# Top.net
KiCad netlist of a schematic drawn in EasyEDA
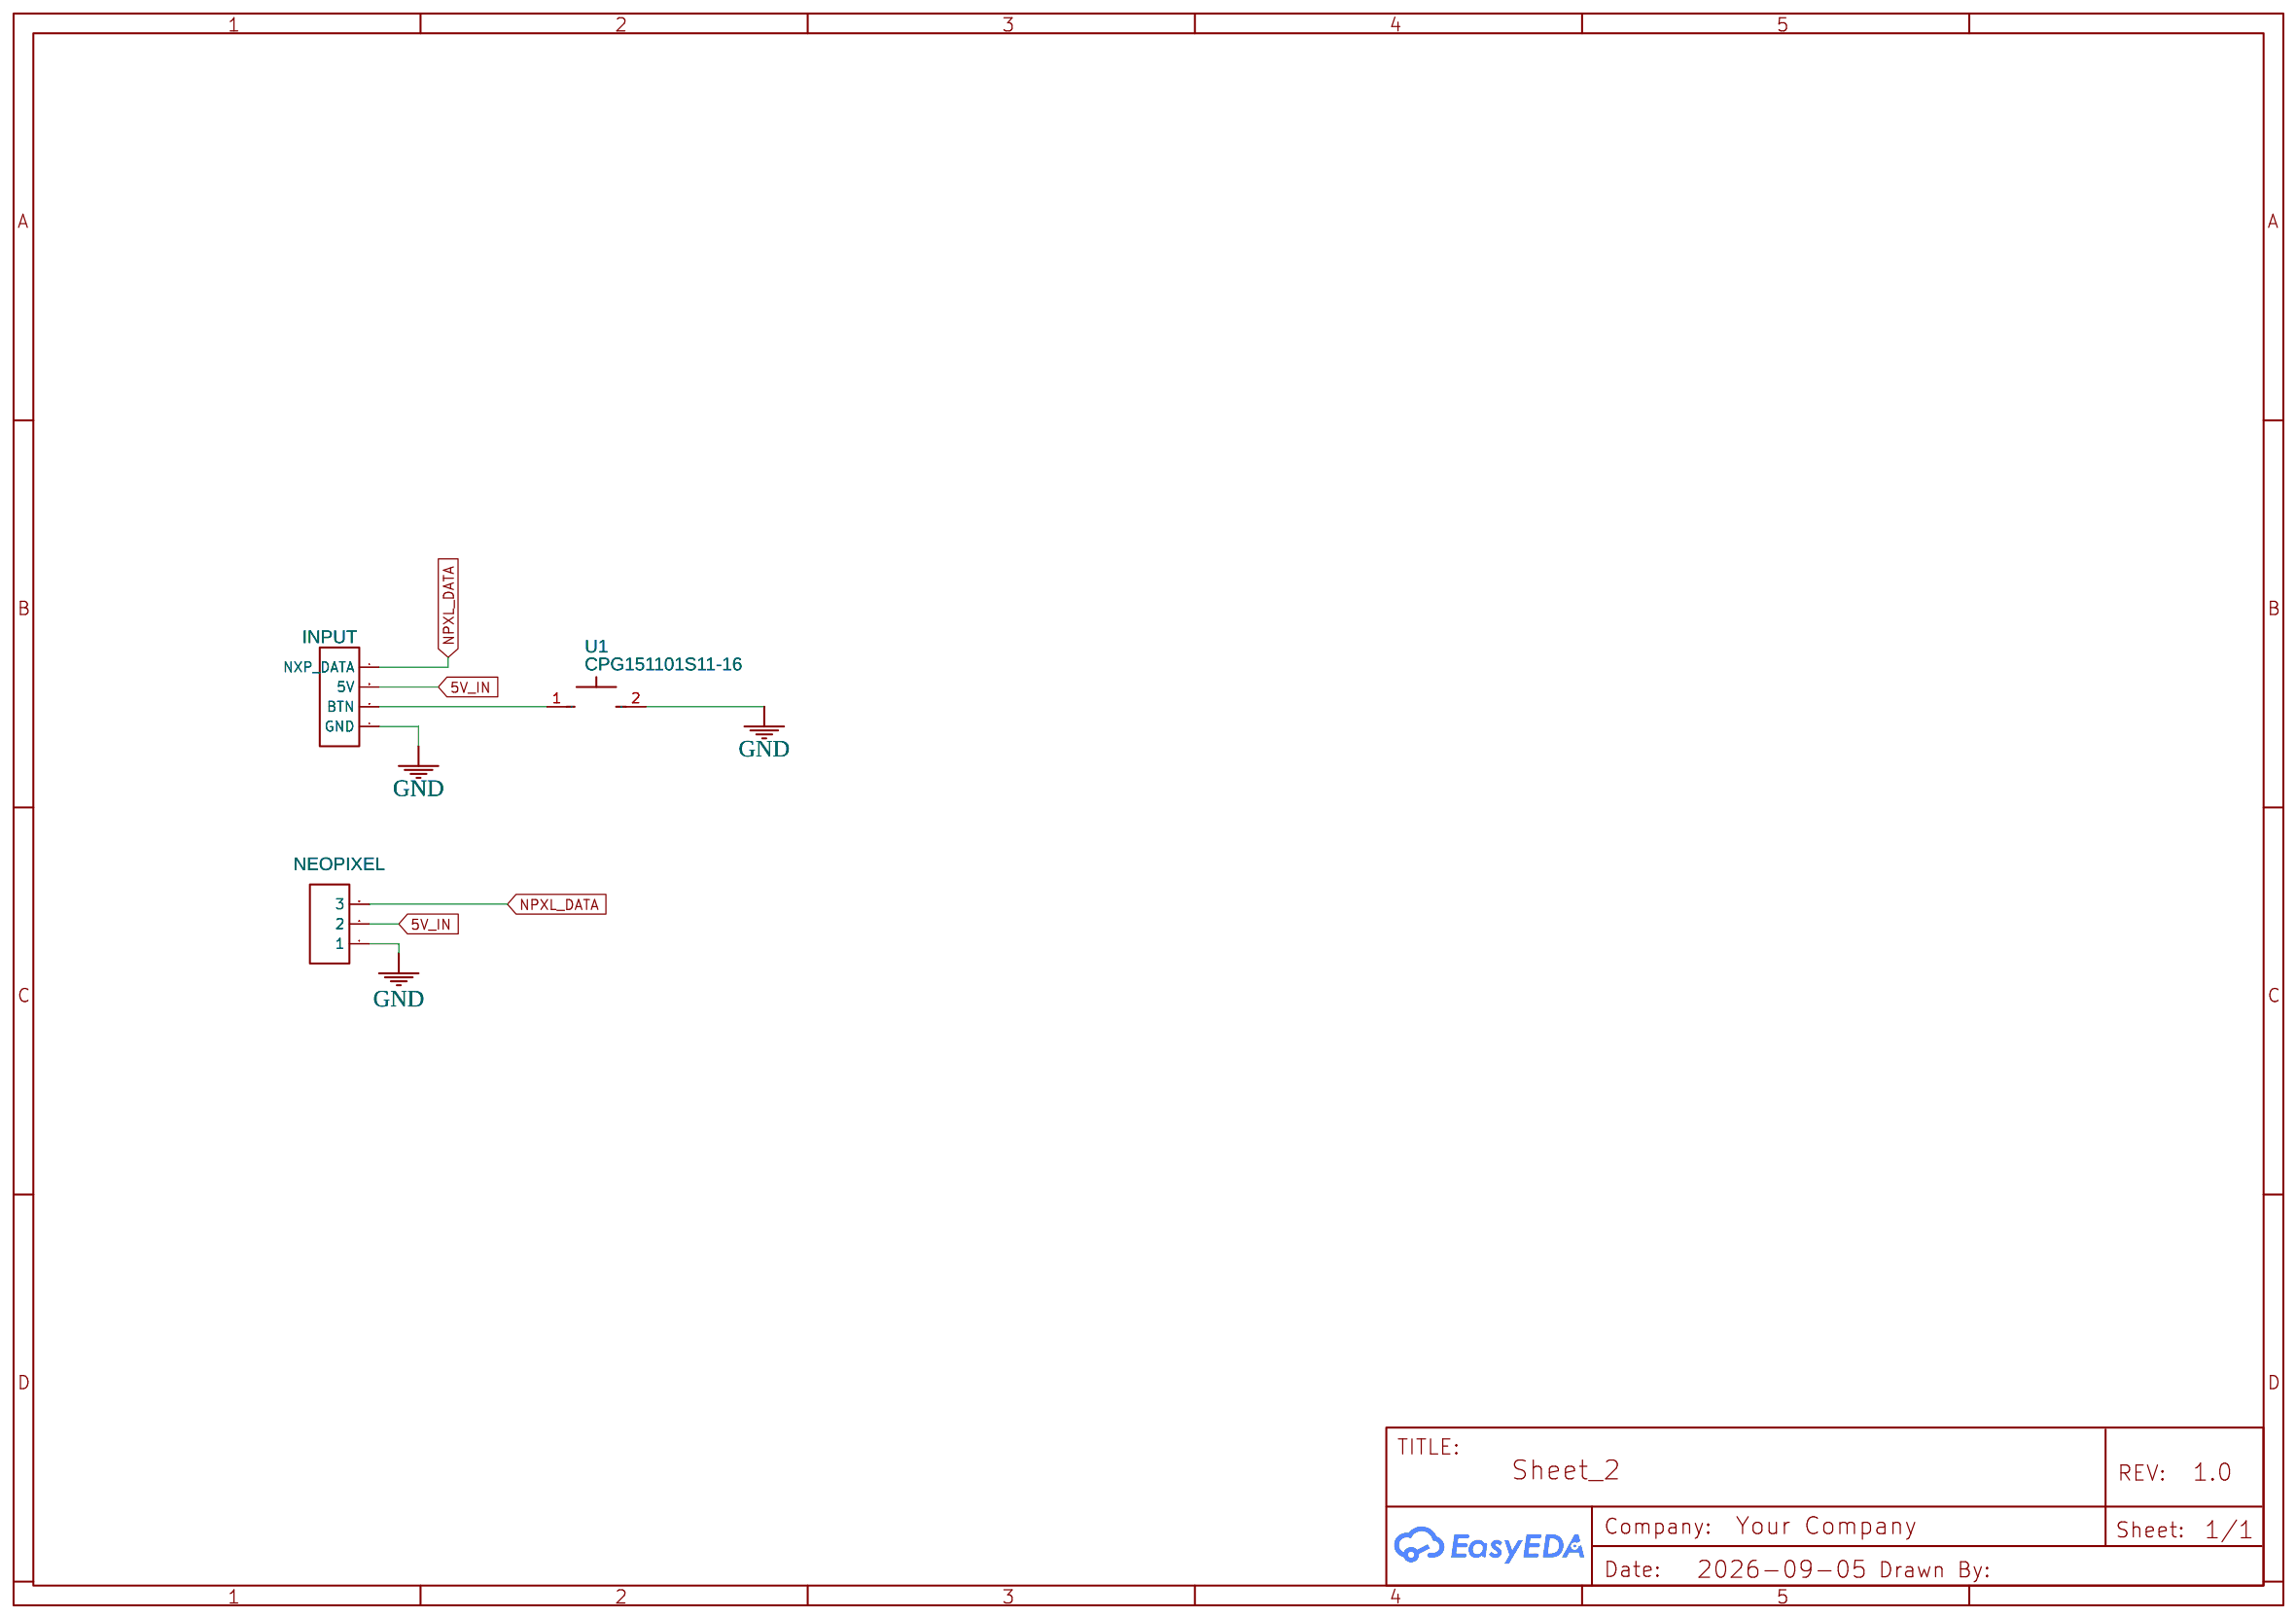
[diagram p0: schematic sheet]

(export (version "E")
  (design (tool "Eeschema 10.0.6"))
  (components
    (comp (ref "INPUT") (value "output") (libsource (lib "") (part "HDR-F-2.54_1x4")))
    (comp (ref "NEOPIXEL") (value "NEOPIXEL") (libsource (lib "") (part "HDR-F-2.54_1x3")))
    (comp (ref "U1")
      (value "CPG151101S11-16")
      (fields (field (name "Manufacturer") "Kailh(凯华)"))
      (libsource (lib "") (part "CPG151101S11-16"))
    )
  )
  (nets
    (net (code "1") (name "5V_IN") (class "Default")
      (node (ref "INPUT") (pin "3") (pinfunction "5V_3") (pintype "unspecified"))
      (node (ref "NEOPIXEL") (pin "2") (pinfunction "2_2") (pintype "input"))
    )
    (net (code "2") (name "GND") (class "Default")
      (node (ref "INPUT") (pin "1") (pinfunction "GND_1") (pintype "unspecified"))
      (node (ref "NEOPIXEL") (pin "1") (pinfunction "1_1") (pintype "input"))
      (node (ref "U1") (pin "2") (pinfunction "2_2") (pintype "input"))
    )
    (net (code "3") (name "NPXL_DATA") (class "Default")
      (node (ref "INPUT") (pin "4") (pinfunction "NXP_DATA_4") (pintype "unspecified"))
      (node (ref "NEOPIXEL") (pin "3") (pinfunction "3_3") (pintype "input"))
    )
    (net (code "4") (name "Net-(INPUT-BTN)") (class "Default")
      (node (ref "INPUT") (pin "2") (pinfunction "BTN_2") (pintype "unspecified"))
      (node (ref "U1") (pin "1") (pinfunction "1_1") (pintype "input"))
    )
  )
)
